# KillSwitch.net
KiCad netlist of a schematic drawn in Altium Designer
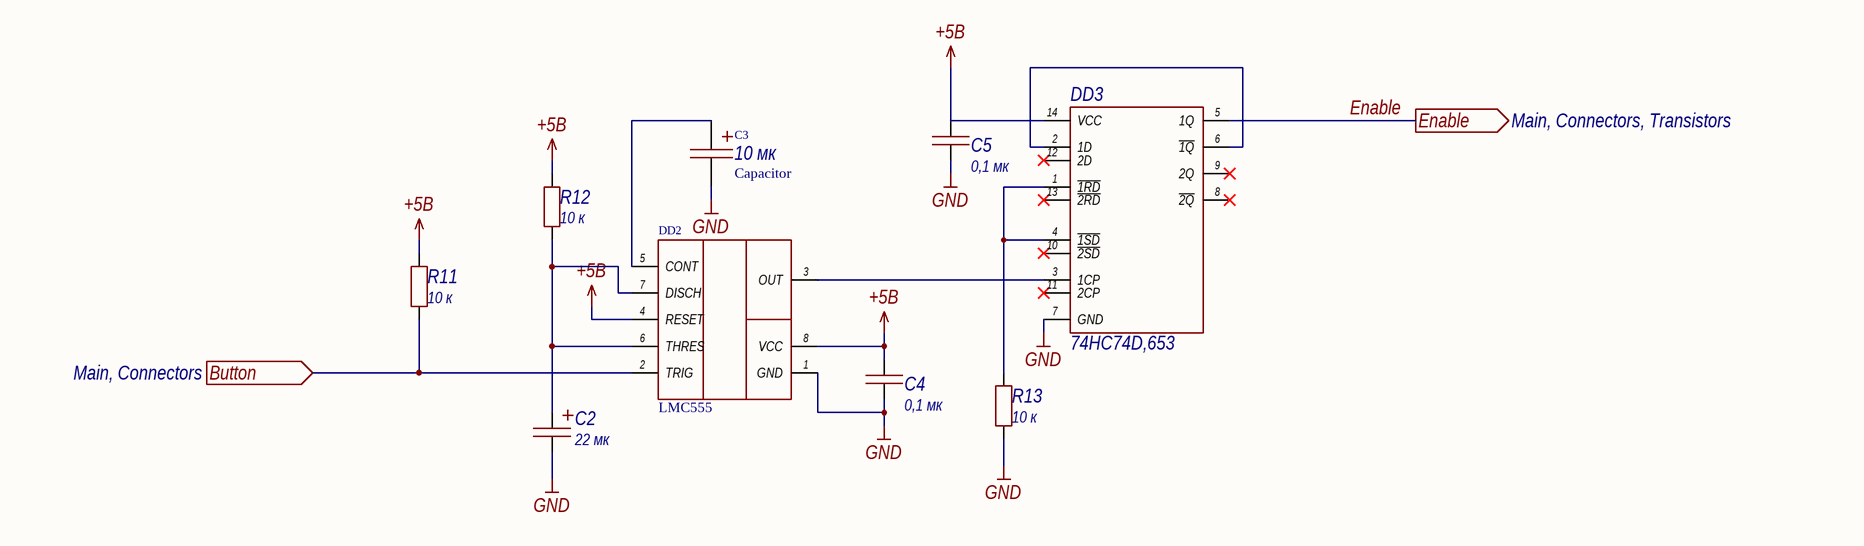
[diagram p0: KillSwitch.SchDoc]

(export (version "E")
  (design (tool "Eeschema 10.0.6"))
  (components
    (comp (ref "C2")
      (value "22 мк")
      (footprint "TC_A")
      (description "Танталовый конденсатор")
      (fields (field (name "PART NUMBER") "Capacitor_22u_10_50V_TC_A") (field (name "TOLERANCE") "0,1"))
      (libsource (lib "") (part "Capacitor_polar_1"))
    )
    (comp (ref "C3")
      (value "Capacitor")
      (footprint "TC_A")
      (description "Танталовый конденсатор")
      (fields
        (field (name "ALTIUM_VALUE") "10 мк")
        (field (name "PART NUMBER") "Capacitor_10u_10_50V_TC_A")
        (field (name "TOLERANCE") "0,1")
      )
      (libsource (lib "Hydrolib") (part "Capacitor_polar"))
    )
    (comp (ref "C4")
      (value "0,1 мк")
      (footprint "0603C")
      (description "Конденсатор")
      (fields (field (name "PART NUMBER") "Capacitor_0,1u_10_50V_X7R_0603C") (field (name "TOLERANCE") "0,1"))
      (libsource (lib "Hydrolib") (part "Capacitor"))
    )
    (comp (ref "C5")
      (value "0,1 мк")
      (footprint "0603C")
      (description "Конденсатор")
      (fields (field (name "PART NUMBER") "Capacitor_0,1u_10_50V_X7R_0603C") (field (name "TOLERANCE") "0,1"))
      (libsource (lib "Hydrolib") (part "Capacitor"))
    )
    (comp (ref "DD2")
      (value "LMC555")
      (footprint "SOIC-8")
      (description "Таймер интегральный прецизионный КМОП")
      (libsource (lib "Hydrolib") (part "NE555"))
    )
    (comp (ref "DD3")
      (value "74HC74D,653")
      (footprint "SOIC-14")
      (description "Два триггера D-типа")
      (fields (field (name "MF") "Nexperia USA"))
      (libsource (lib "Hydrolib") (part "74HC74D,653"))
    )
    (comp (ref "R11")
      (value "10 к")
      (footprint "0603R")
      (description "Резистор номиналом 10 кОм и точностью 1%")
      (fields (field (name "PART NUMBER") "Resistor_10k_1_0603") (field (name "TOLERANCE") "1%"))
      (libsource (lib "Hydrolib") (part "Resistor"))
    )
    (comp (ref "R12")
      (value "10 к")
      (footprint "0603R")
      (description "Резистор номиналом 10 кОм и точностью 1%")
      (fields (field (name "PART NUMBER") "Resistor_10k_1_0603") (field (name "TOLERANCE") "1%"))
      (libsource (lib "Hydrolib") (part "Resistor"))
    )
    (comp (ref "R13")
      (value "10 к")
      (footprint "0603R")
      (description "Резистор номиналом 10 кОм и точностью 1%")
      (fields (field (name "PART NUMBER") "Resistor_10k_1_0603") (field (name "TOLERANCE") "1%"))
      (libsource (lib "Hydrolib") (part "Resistor"))
    )
  )
  (nets
    (net (code "1") (name "+5В") (class "Default")
      (node (ref "C4") (pin "2") (pinfunction "2_2") (pintype "passive"))
      (node (ref "C5") (pin "1") (pinfunction "1_1") (pintype "passive"))
      (node (ref "DD2") (pin "4") (pinfunction "RESET_4") (pintype "passive"))
      (node (ref "DD2") (pin "8") (pinfunction "VCC_8") (pintype "passive"))
      (node (ref "DD3") (pin "14") (pinfunction "VCC_14") (pintype "passive"))
      (node (ref "R11") (pin "2") (pinfunction "2_2") (pintype "passive"))
      (node (ref "R12") (pin "2") (pinfunction "2_2") (pintype "passive"))
    )
    (net (code "2") (name "/Button") (class "Default")
      (node (ref "DD2") (pin "2") (pinfunction "TRIG_2") (pintype "passive"))
      (node (ref "R11") (pin "1") (pinfunction "1_1") (pintype "passive"))
    )
    (net (code "3") (name "/Enable") (class "Default")
      (node (ref "DD3") (pin "5") (pinfunction "1Q_5") (pintype "passive"))
    )
    (net (code "4") (name "GND") (class "Default")
      (node (ref "C2") (pin "2") (pinfunction "2_2") (pintype "passive"))
      (node (ref "C3") (pin "2") (pinfunction "2_2") (pintype "passive"))
      (node (ref "C4") (pin "1") (pinfunction "1_1") (pintype "passive"))
      (node (ref "C5") (pin "2") (pinfunction "2_2") (pintype "passive"))
      (node (ref "DD2") (pin "1") (pinfunction "GND_1") (pintype "passive"))
      (node (ref "DD3") (pin "7") (pinfunction "GND_7") (pintype "passive"))
      (node (ref "R13") (pin "1") (pinfunction "1_1") (pintype "passive"))
    )
    (net (code "5") (name "Net-(DD2-CONT)") (class "Default")
      (node (ref "C3") (pin "1") (pinfunction "1_1") (pintype "passive"))
      (node (ref "DD2") (pin "5") (pinfunction "CONT_5") (pintype "passive"))
    )
    (net (code "6") (name "Net-(DD2-DISCH)") (class "Default")
      (node (ref "C2") (pin "1") (pinfunction "1_1") (pintype "passive"))
      (node (ref "DD2") (pin "6") (pinfunction "THRES_6") (pintype "passive"))
      (node (ref "DD2") (pin "7") (pinfunction "DISCH_7") (pintype "passive"))
      (node (ref "R12") (pin "1") (pinfunction "1_1") (pintype "passive"))
    )
    (net (code "7") (name "Net-(DD2-OUT)") (class "Default")
      (node (ref "DD2") (pin "3") (pinfunction "OUT_3") (pintype "passive"))
      (node (ref "DD3") (pin "3") (pinfunction "1CP_3") (pintype "passive"))
    )
    (net (code "8") (name "Net-(DD3-1D)") (class "Default")
      (node (ref "DD3") (pin "2") (pinfunction "1D_2") (pintype "passive"))
      (node (ref "DD3") (pin "6") (pinfunction "~{1Q}_6") (pintype "passive"))
    )
    (net (code "9") (name "Net-(DD3-~{1RD})") (class "Default")
      (node (ref "DD3") (pin "1") (pinfunction "~{1RD}_1") (pintype "passive"))
      (node (ref "DD3") (pin "4") (pinfunction "~{1SD}_4") (pintype "passive"))
      (node (ref "R13") (pin "2") (pinfunction "2_2") (pintype "passive"))
    )
    (net (code "10") (name "unconnected-(DD3-2CP-Pad11)") (class "Default")
      (node (ref "DD3") (pin "11") (pinfunction "2CP_11") (pintype "passive+no_connect"))
    )
    (net (code "11") (name "unconnected-(DD3-2D-Pad12)") (class "Default")
      (node (ref "DD3") (pin "12") (pinfunction "2D_12") (pintype "passive+no_connect"))
    )
    (net (code "12") (name "unconnected-(DD3-2Q-Pad9)") (class "Default")
      (node (ref "DD3") (pin "9") (pinfunction "2Q_9") (pintype "passive+no_connect"))
    )
    (net (code "13") (name "unconnected-(DD3-~{2Q}-Pad8)") (class "Default")
      (node (ref "DD3") (pin "8") (pinfunction "~{2Q}_8") (pintype "passive+no_connect"))
    )
    (net (code "14") (name "unconnected-(DD3-~{2RD}-Pad13)") (class "Default")
      (node (ref "DD3") (pin "13") (pinfunction "~{2RD}_13") (pintype "passive+no_connect"))
    )
    (net (code "15") (name "unconnected-(DD3-~{2SD}-Pad10)") (class "Default")
      (node (ref "DD3") (pin "10") (pinfunction "~{2SD}_10") (pintype "passive+no_connect"))
    )
  )
)
